# pi_backback.net
KiCad netlist of a schematic drawn in EAGLE
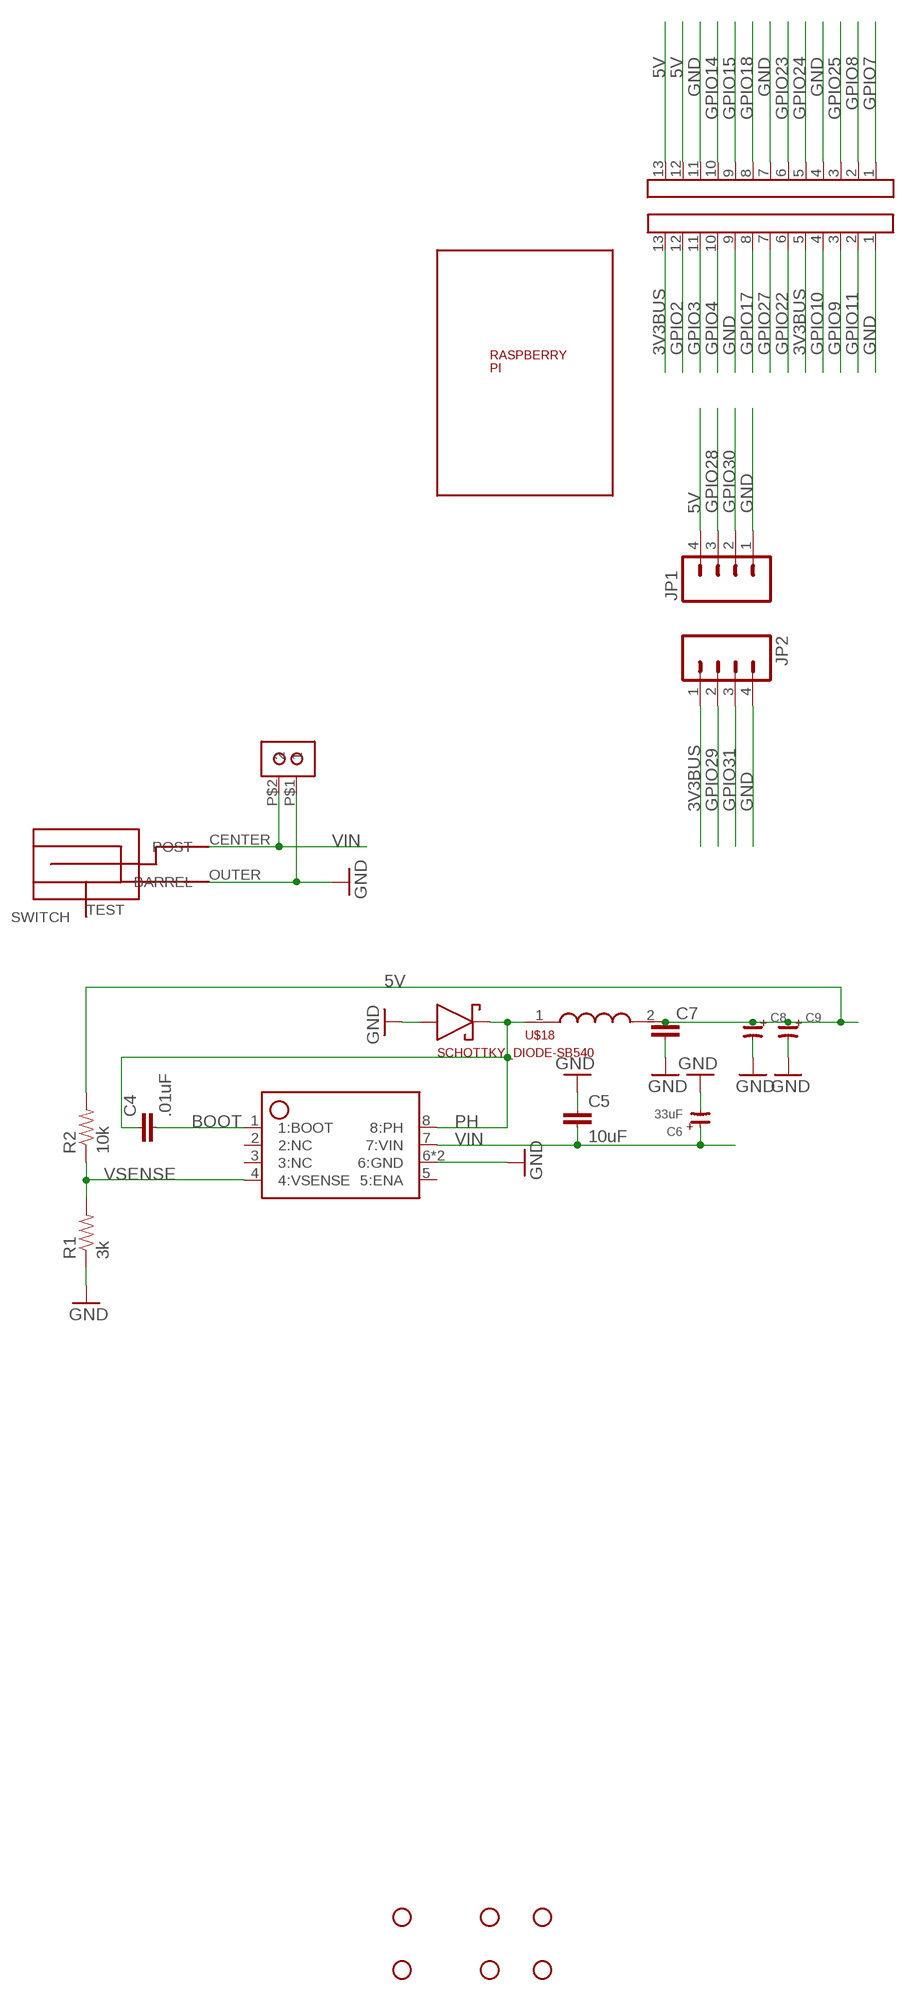
[diagram p0: schematic, sheet 1, part 1 of 2]
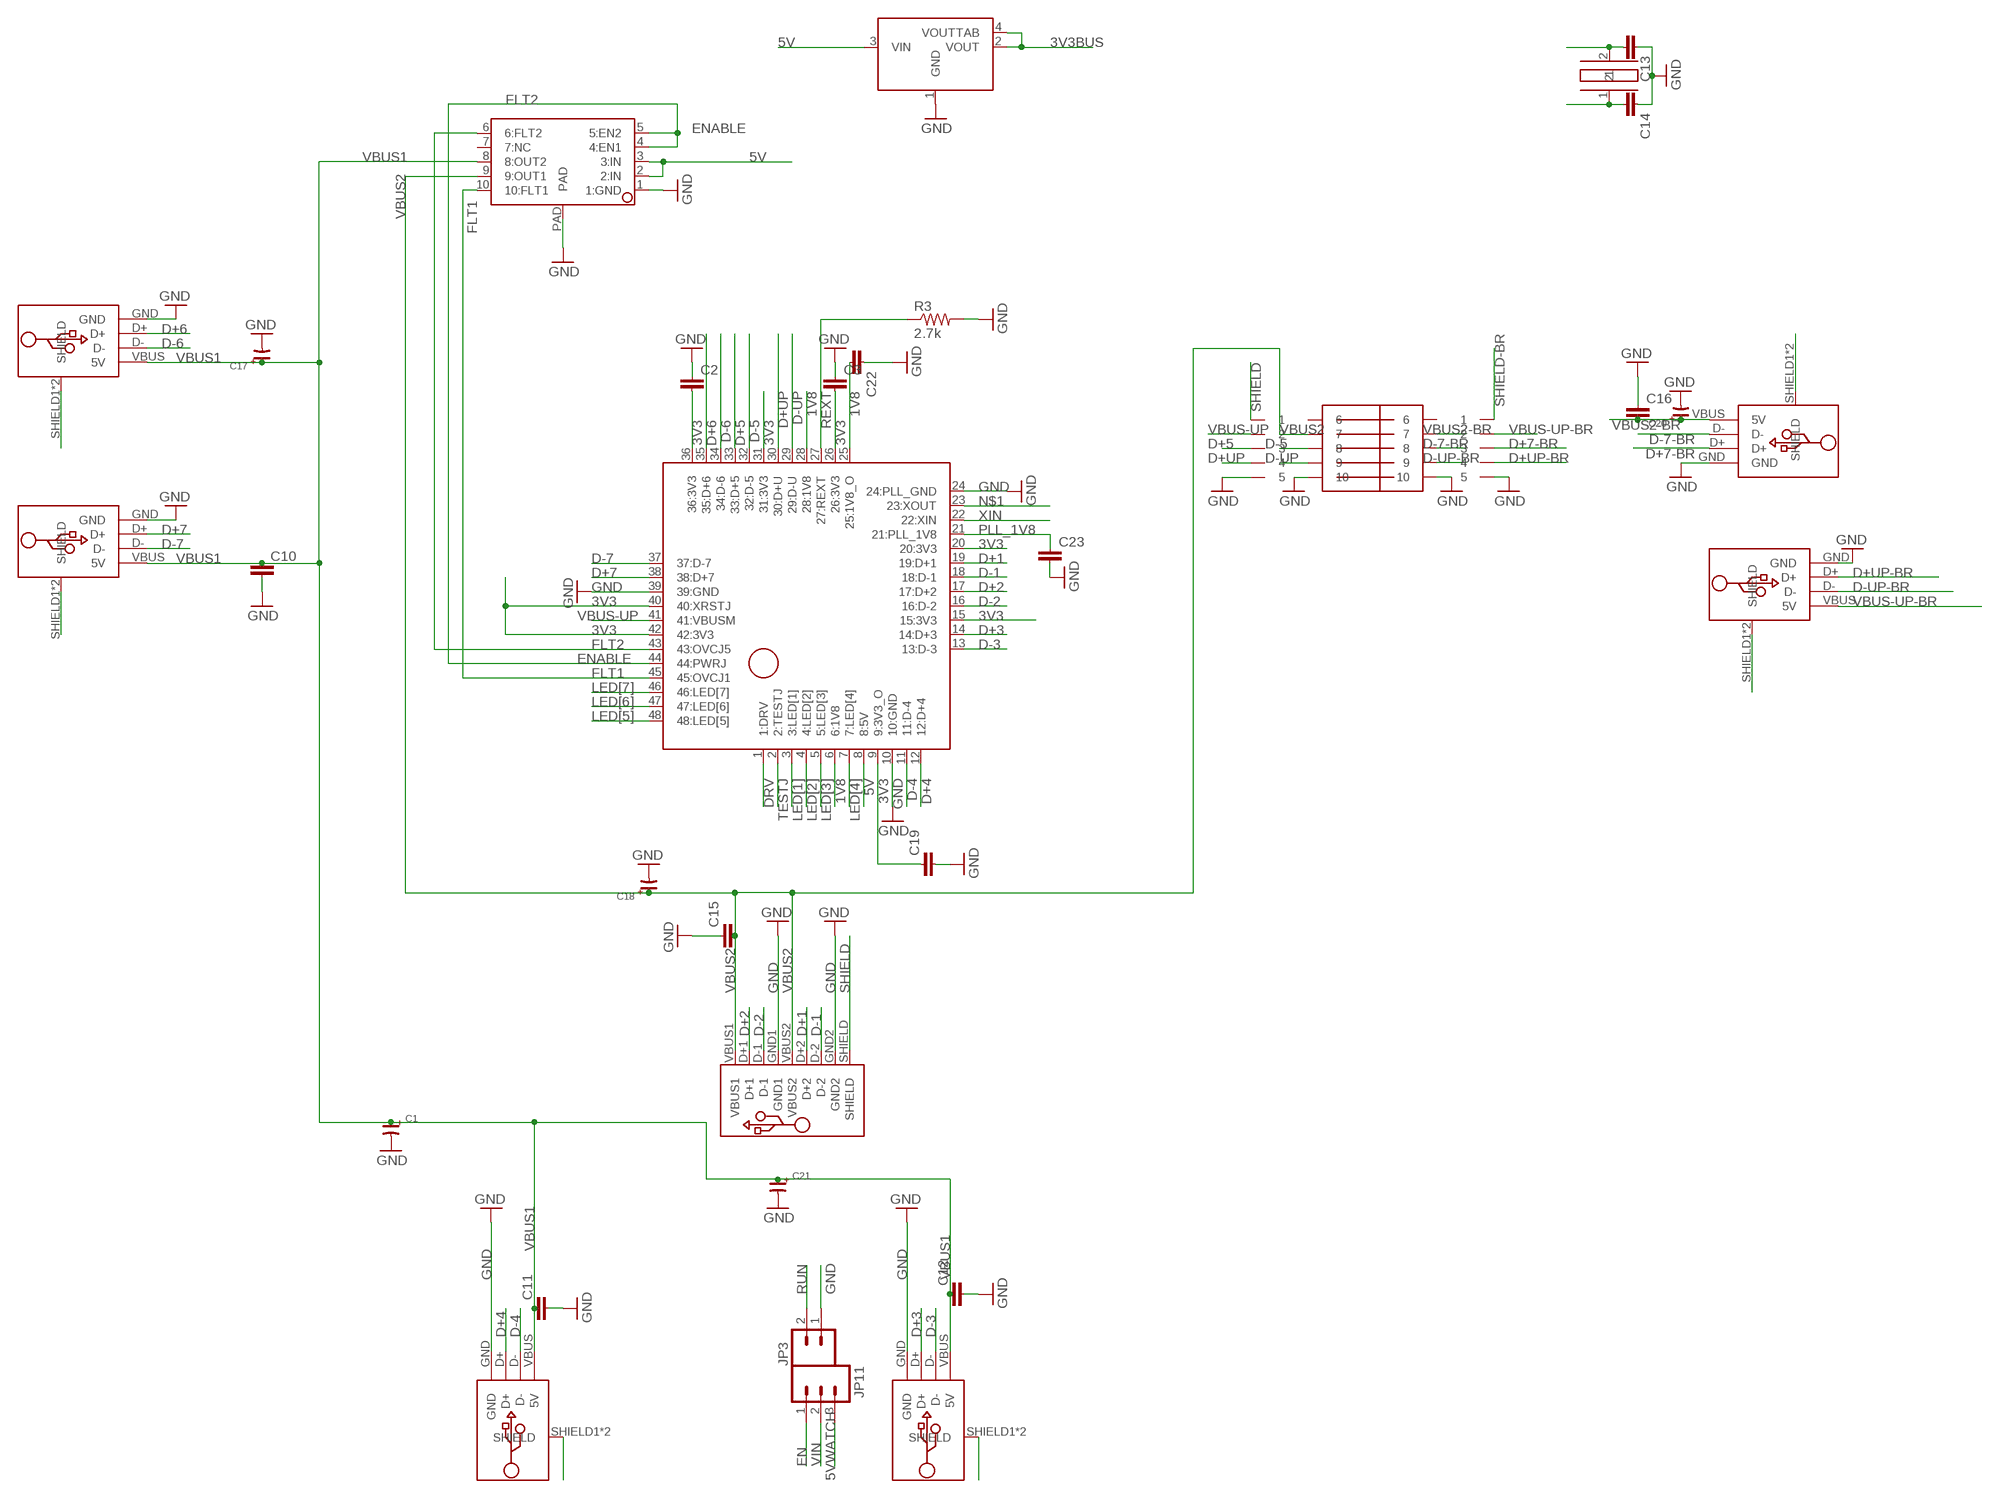
[diagram p1: schematic, sheet 1, part 2 of 2]

(export (version "E")
  (design (tool "Eeschema 10.0.6"))
  (components
    (comp (ref "C1")
      (value "CAPPOL-5X11")
      (footprint "eagle-import:5X11MMCAP")
      (libsource (lib "eagle-import") (part "CAPPOL-5X11"))
    )
    (comp (ref "C2")
      (value "CAP0805")
      (footprint "eagle-import:0805")
      (libsource (lib "eagle-import") (part "CAP0805"))
    )
    (comp (ref "C3")
      (value "CAP0805")
      (footprint "eagle-import:0805")
      (libsource (lib "eagle-import") (part "CAP0805"))
    )
    (comp (ref "C4")
      (value ".01uF")
      (footprint "eagle-import:0603-CAP")
      (libsource (lib "eagle-import") (part "CAP0603-CAP"))
    )
    (comp (ref "C5")
      (value "10uF")
      (footprint "eagle-import:1206")
      (libsource (lib "eagle-import") (part "CAP1206"))
    )
    (comp (ref "C6")
      (value "33uF")
      (footprint "eagle-import:8MMCAP")
      (libsource (lib "eagle-import") (part "CAPPOL-8X11"))
    )
    (comp (ref "C7")
      (value "CAP1206")
      (footprint "eagle-import:1206")
      (libsource (lib "eagle-import") (part "CAP1206"))
    )
    (comp (ref "C8")
      (value "CAPPOL-XX6.3")
      (footprint "eagle-import:6.3MMDIAMELECTROLYTIC")
      (libsource (lib "eagle-import") (part "CAPPOL-XX6.3"))
    )
    (comp (ref "C9")
      (value "CAPPOL-XX6.3")
      (footprint "eagle-import:6.3MMDIAMELECTROLYTIC")
      (libsource (lib "eagle-import") (part "CAPPOL-XX6.3"))
    )
    (comp (ref "C10")
      (value "CAP0805")
      (footprint "eagle-import:0805")
      (libsource (lib "eagle-import") (part "CAP0805"))
    )
    (comp (ref "C11")
      (value "CAP0805")
      (footprint "eagle-import:0805")
      (libsource (lib "eagle-import") (part "CAP0805"))
    )
    (comp (ref "C12")
      (value "CAP0805")
      (footprint "eagle-import:0805")
      (libsource (lib "eagle-import") (part "CAP0805"))
    )
    (comp (ref "C13")
      (value "CAP0603-CAP")
      (footprint "eagle-import:0603-CAP")
      (libsource (lib "eagle-import") (part "CAP0603-CAP"))
    )
    (comp (ref "C14")
      (value "CAP0603-CAP")
      (footprint "eagle-import:0603-CAP")
      (libsource (lib "eagle-import") (part "CAP0603-CAP"))
    )
    (comp (ref "C15")
      (value "CAP0805")
      (footprint "eagle-import:0805")
      (libsource (lib "eagle-import") (part "CAP0805"))
    )
    (comp (ref "C16")
      (value "CAP0805")
      (footprint "eagle-import:0805")
      (libsource (lib "eagle-import") (part "CAP0805"))
    )
    (comp (ref "C17")
      (value "CAPPOL-5X11")
      (footprint "eagle-import:5X11MMCAP")
      (libsource (lib "eagle-import") (part "CAPPOL-5X11"))
    )
    (comp (ref "C18")
      (value "CAPPOL-5X11")
      (footprint "eagle-import:5X11MMCAP")
      (libsource (lib "eagle-import") (part "CAPPOL-5X11"))
    )
    (comp (ref "C19")
      (value "CAP1206")
      (footprint "eagle-import:1206")
      (libsource (lib "eagle-import") (part "CAP1206"))
    )
    (comp (ref "C20")
      (value "CAPPOL-5X11")
      (footprint "eagle-import:5X11MMCAP")
      (libsource (lib "eagle-import") (part "CAPPOL-5X11"))
    )
    (comp (ref "C21")
      (value "CAPPOL-5X11")
      (footprint "eagle-import:5X11MMCAP")
      (libsource (lib "eagle-import") (part "CAPPOL-5X11"))
    )
    (comp (ref "C22")
      (value "CAP1206")
      (footprint "eagle-import:1206")
      (libsource (lib "eagle-import") (part "CAP1206"))
    )
    (comp (ref "C23")
      (value "CAP0805")
      (footprint "eagle-import:0805")
      (libsource (lib "eagle-import") (part "CAP0805"))
    )
    (comp (ref "JP1")
      (value "M04LOCK")
      (footprint "eagle-import:1X04_LOCK")
      (libsource (lib "eagle-import") (part "M04LOCK"))
    )
    (comp (ref "JP2")
      (value "M04LOCK")
      (footprint "eagle-import:1X04_LOCK")
      (libsource (lib "eagle-import") (part "M04LOCK"))
    )
    (comp (ref "JP3")
      (value "M02LOCK")
      (footprint "eagle-import:1X02_LOCK")
      (libsource (lib "eagle-import") (part "M02LOCK"))
    )
    (comp (ref "JP4")
      (value "STAND-OFFTIGHT")
      (footprint "eagle-import:STAND-OFF-TIGHT")
      (libsource (lib "eagle-import") (part "STAND-OFFTIGHT"))
    )
    (comp (ref "JP5")
      (value "STAND-OFFTIGHT")
      (footprint "eagle-import:STAND-OFF-TIGHT")
      (libsource (lib "eagle-import") (part "STAND-OFFTIGHT"))
    )
    (comp (ref "JP6")
      (value "STAND-OFFTIGHT")
      (footprint "eagle-import:STAND-OFF-TIGHT")
      (libsource (lib "eagle-import") (part "STAND-OFFTIGHT"))
    )
    (comp (ref "JP7")
      (value "STAND-OFFTIGHT")
      (footprint "eagle-import:STAND-OFF-TIGHT")
      (libsource (lib "eagle-import") (part "STAND-OFFTIGHT"))
    )
    (comp (ref "JP9")
      (value "STAND-OFFTIGHT")
      (footprint "eagle-import:STAND-OFF-TIGHT")
      (libsource (lib "eagle-import") (part "STAND-OFFTIGHT"))
    )
    (comp (ref "JP10")
      (value "STAND-OFFTIGHT")
      (footprint "eagle-import:STAND-OFF-TIGHT")
      (libsource (lib "eagle-import") (part "STAND-OFFTIGHT"))
    )
    (comp (ref "JP11")
      (value "M03LOCK")
      (footprint "eagle-import:1X03_LOCK")
      (libsource (lib "eagle-import") (part "M03LOCK"))
    )
    (comp (ref "R1")
      (value "3k")
      (footprint "eagle-import:0805")
      (libsource (lib "eagle-import") (part "RESISTOR"))
    )
    (comp (ref "R2")
      (value "10k")
      (footprint "eagle-import:0805")
      (libsource (lib "eagle-import") (part "RESISTOR"))
    )
    (comp (ref "R3")
      (value "2.7k")
      (footprint "eagle-import:0805")
      (libsource (lib "eagle-import") (part "RESISTOR"))
    )
    (comp (ref "U$1")
      (value "RASPBERRY-PI-OUTLINE")
      (footprint "eagle-import:RASPBERRY-PI-REV2-OUTLINE")
      (libsource (lib "eagle-import") (part "RASPBERRY-PI-OUTLINE"))
    )
    (comp (ref "U$2")
      (value "M13")
      (footprint "eagle-import:1X13_LOCK")
      (libsource (lib "eagle-import") (part "M13"))
    )
    (comp (ref "U$3")
      (value "M13")
      (footprint "eagle-import:1X13_LOCK")
      (libsource (lib "eagle-import") (part "M13"))
    )
    (comp (ref "U$4")
      (value "TPS200(2/3)C")
      (footprint "eagle-import:SON-10")
      (libsource (lib "eagle-import") (part "TPS200(2/3)C"))
    )
    (comp (ref "U$5")
      (value "FE2.1-48")
      (footprint "eagle-import:LQFP-48")
      (libsource (lib "eagle-import") (part "FE2.1-48"))
    )
    (comp (ref "U$6")
      (value "USB-A-MALE")
      (footprint "eagle-import:USB-A-MALE")
      (libsource (lib "eagle-import") (part "USB-A-MALE"))
    )
    (comp (ref "U$7")
      (value "SCREWTERM-2MA212-2")
      (footprint "eagle-import:MA212-2")
      (libsource (lib "eagle-import") (part "SCREWTERM-2MA212-2"))
    )
    (comp (ref "U$8")
      (value "USB-A-FEMALE")
      (footprint "eagle-import:USB-A-FEMALE")
      (libsource (lib "eagle-import") (part "USB-A-FEMALE"))
    )
    (comp (ref "U$9")
      (value "USB-A-FEMALE")
      (footprint "eagle-import:USB-A-FEMALE")
      (libsource (lib "eagle-import") (part "USB-A-FEMALE"))
    )
    (comp (ref "U$10")
      (value "USB-A-FEMALE")
      (footprint "eagle-import:USB-A-FEMALE")
      (libsource (lib "eagle-import") (part "USB-A-FEMALE"))
    )
    (comp (ref "U$11")
      (value "USB_HEADER")
      (footprint "eagle-import:USB_HEADER")
      (libsource (lib "eagle-import") (part "USB_HEADER"))
    )
    (comp (ref "U$12")
      (value "USB-A-FEMALE")
      (footprint "eagle-import:USB-A-FEMALE")
      (libsource (lib "eagle-import") (part "USB-A-FEMALE"))
    )
    (comp (ref "U$13")
      (value "TPS5450")
      (footprint "eagle-import:SOIC8-POWERPAD")
      (libsource (lib "eagle-import") (part "TPS5450"))
    )
    (comp (ref "U$14")
      (value "M05X02_FEM-LOCK_RIGHT_ANGLE_FEM")
      (footprint "eagle-import:2X05_LOCK_RIGHT_ANGLE_FEM")
      (libsource (lib "eagle-import") (part "M05X02_FEM-LOCK_RIGHT_ANGLE_FEM"))
    )
    (comp (ref "U$15")
      (value "M05X02_MALE")
      (footprint "eagle-import:2X05_LOCK_RIGHT_ANGLE_MALE")
      (libsource (lib "eagle-import") (part "M05X02_MALE"))
    )
    (comp (ref "U$16")
      (value "USB-A-FEMALE")
      (footprint "eagle-import:USB-A-FEMALE")
      (libsource (lib "eagle-import") (part "USB-A-FEMALE"))
    )
    (comp (ref "U$17")
      (value "POWER-JACK-2.1MM")
      (footprint "eagle-import:2.1MM-POWER-JACK")
      (libsource (lib "eagle-import") (part "POWER-JACK-2.1MM"))
    )
    (comp (ref "U$18")
      (value "INDUCTOR-DR13-RT-A")
      (footprint "eagle-import:DR13-RT-A")
      (libsource (lib "eagle-import") (part "INDUCTOR-DR13-RT-A"))
    )
    (comp (ref "U$19")
      (value "SCHOTTKY_DIODE-SB540")
      (footprint "eagle-import:DO-201-AD")
      (libsource (lib "eagle-import") (part "SCHOTTKY_DIODE-SB540"))
    )
    (comp (ref "U$20")
      (value "CRYSTAL-HC49")
      (footprint "eagle-import:HC49US")
      (libsource (lib "eagle-import") (part "CRYSTAL-HC49"))
    )
    (comp (ref "U$21")
      (value "3V3-LDO-ZLDO1117")
      (footprint "eagle-import:ZLDO1117")
      (libsource (lib "eagle-import") (part "3V3-LDO-ZLDO1117"))
    )
  )
  (nets
    (net (code "1") (name "/1V8") (class "Default")
      (node (ref "C22") (pin "2") (pinfunction "2_2") (pintype "passive"))
      (node (ref "U$5") (pin "25") (pinfunction "25:1V8_O_25") (pintype "bidirectional"))
      (node (ref "U$5") (pin "28") (pinfunction "28:1V8_28") (pintype "bidirectional"))
      (node (ref "U$5") (pin "6") (pinfunction "6:1V8_6") (pintype "bidirectional"))
    )
    (net (code "2") (name "/3V3") (class "Default")
      (node (ref "C19") (pin "1") (pinfunction "1_1") (pintype "passive"))
      (node (ref "C2") (pin "2") (pinfunction "2_2") (pintype "passive"))
      (node (ref "C3") (pin "2") (pinfunction "2_2") (pintype "passive"))
      (node (ref "U$5") (pin "15") (pinfunction "15:3V3_15") (pintype "bidirectional"))
      (node (ref "U$5") (pin "20") (pinfunction "20:3V3_20") (pintype "bidirectional"))
      (node (ref "U$5") (pin "26") (pinfunction "26:3V3_26") (pintype "bidirectional"))
      (node (ref "U$5") (pin "31") (pinfunction "31:3V3_31") (pintype "bidirectional"))
      (node (ref "U$5") (pin "36") (pinfunction "36:3V3_36") (pintype "bidirectional"))
      (node (ref "U$5") (pin "40") (pinfunction "40:XRSTJ_40") (pintype "bidirectional"))
      (node (ref "U$5") (pin "42") (pinfunction "42:3V3_42") (pintype "bidirectional"))
      (node (ref "U$5") (pin "9") (pinfunction "9:3V3_O_9") (pintype "bidirectional"))
    )
    (net (code "3") (name "/3V3BUS") (class "Default")
      (node (ref "JP2") (pin "1") (pinfunction "1_1") (pintype "passive"))
      (node (ref "U$2") (pin "13") (pinfunction "13_13") (pintype "bidirectional"))
      (node (ref "U$2") (pin "5") (pinfunction "5_5") (pintype "bidirectional"))
      (node (ref "U$21") (pin "2") (pinfunction "VOUT_2") (pintype "bidirectional"))
      (node (ref "U$21") (pin "4") (pinfunction "VOUTTAB_4") (pintype "bidirectional"))
    )
    (net (code "4") (name "/5V") (class "Default")
      (node (ref "C7") (pin "1") (pinfunction "1_1") (pintype "passive"))
      (node (ref "C8") (pin "+") (pinfunction "+_+") (pintype "bidirectional"))
      (node (ref "C9") (pin "+") (pinfunction "+_+") (pintype "bidirectional"))
      (node (ref "JP1") (pin "4") (pinfunction "4_4") (pintype "passive"))
      (node (ref "R2") (pin "2") (pinfunction "2_2") (pintype "passive"))
      (node (ref "U$18") (pin "2") (pinfunction "P$2_2") (pintype "bidirectional"))
      (node (ref "U$21") (pin "3") (pinfunction "VIN_3") (pintype "bidirectional"))
      (node (ref "U$3") (pin "12") (pinfunction "12_12") (pintype "bidirectional"))
      (node (ref "U$3") (pin "13") (pinfunction "13_13") (pintype "bidirectional"))
      (node (ref "U$4") (pin "2") (pinfunction "2:IN_2") (pintype "bidirectional"))
      (node (ref "U$4") (pin "3") (pinfunction "3:IN_3") (pintype "bidirectional"))
      (node (ref "U$5") (pin "8") (pinfunction "8:5V_8") (pintype "bidirectional"))
    )
    (net (code "5") (name "/5VWATCH") (class "Default")
      (node (ref "JP11") (pin "3") (pinfunction "3_3") (pintype "passive"))
    )
    (net (code "6") (name "/BOOT") (class "Default")
      (node (ref "C4") (pin "2") (pinfunction "2_2") (pintype "passive"))
      (node (ref "U$13") (pin "1") (pinfunction "1:BOOT_1") (pintype "bidirectional"))
    )
    (net (code "7") (name "/D+1") (class "Default")
      (node (ref "U$11") (pin "D+2") (pinfunction "D+2_D+2") (pintype "bidirectional"))
      (node (ref "U$5") (pin "19") (pinfunction "19:D+1_19") (pintype "bidirectional"))
    )
    (net (code "8") (name "/D+2") (class "Default")
      (node (ref "U$11") (pin "D+1") (pinfunction "D+1_D+1") (pintype "bidirectional"))
      (node (ref "U$5") (pin "17") (pinfunction "17:D+2_17") (pintype "bidirectional"))
    )
    (net (code "9") (name "/D+3") (class "Default")
      (node (ref "U$12") (pin "D+") (pinfunction "D+_D+") (pintype "bidirectional"))
      (node (ref "U$5") (pin "14") (pinfunction "14:D+3_14") (pintype "bidirectional"))
    )
    (net (code "10") (name "/D+4") (class "Default")
      (node (ref "U$16") (pin "D+") (pinfunction "D+_D+") (pintype "bidirectional"))
      (node (ref "U$5") (pin "12") (pinfunction "12:D+4_12") (pintype "bidirectional"))
    )
    (net (code "11") (name "/D+5") (class "Default")
      (node (ref "U$14") (pin "3") (pinfunction "3_3") (pintype "bidirectional"))
      (node (ref "U$5") (pin "33") (pinfunction "33:D+5_33") (pintype "bidirectional"))
    )
    (net (code "12") (name "/D+6") (class "Default")
      (node (ref "U$5") (pin "35") (pinfunction "35:D+6_35") (pintype "bidirectional"))
      (node (ref "U$9") (pin "D+") (pinfunction "D+_D+") (pintype "bidirectional"))
    )
    (net (code "13") (name "/D+7") (class "Default")
      (node (ref "U$5") (pin "38") (pinfunction "38:D+7_38") (pintype "bidirectional"))
      (node (ref "U$8") (pin "D+") (pinfunction "D+_D+") (pintype "bidirectional"))
    )
    (net (code "14") (name "/D+7-BR") (class "Default")
      (node (ref "U$10") (pin "D+") (pinfunction "D+_D+") (pintype "bidirectional"))
      (node (ref "U$15") (pin "3") (pinfunction "3_3") (pintype "bidirectional"))
    )
    (net (code "15") (name "/D+UP") (class "Default")
      (node (ref "U$14") (pin "4") (pinfunction "4_4") (pintype "bidirectional"))
      (node (ref "U$5") (pin "30") (pinfunction "30:D+U_30") (pintype "bidirectional"))
    )
    (net (code "16") (name "/D+UP-BR") (class "Default")
      (node (ref "U$15") (pin "4") (pinfunction "4_4") (pintype "bidirectional"))
      (node (ref "U$6") (pin "D+") (pinfunction "D+_D+") (pintype "bidirectional"))
    )
    (net (code "17") (name "/D-1") (class "Default")
      (node (ref "U$11") (pin "D-2") (pinfunction "D-2_D-2") (pintype "bidirectional"))
      (node (ref "U$5") (pin "18") (pinfunction "18:D-1_18") (pintype "bidirectional"))
    )
    (net (code "18") (name "/D-2") (class "Default")
      (node (ref "U$11") (pin "D-1") (pinfunction "D-1_D-1") (pintype "bidirectional"))
      (node (ref "U$5") (pin "16") (pinfunction "16:D-2_16") (pintype "bidirectional"))
    )
    (net (code "19") (name "/D-3") (class "Default")
      (node (ref "U$12") (pin "D-") (pinfunction "D-_D-") (pintype "bidirectional"))
      (node (ref "U$5") (pin "13") (pinfunction "13:D-3_13") (pintype "bidirectional"))
    )
    (net (code "20") (name "/D-4") (class "Default")
      (node (ref "U$16") (pin "D-") (pinfunction "D-_D-") (pintype "bidirectional"))
      (node (ref "U$5") (pin "11") (pinfunction "11:D-4_11") (pintype "bidirectional"))
    )
    (net (code "21") (name "/D-5") (class "Default")
      (node (ref "U$14") (pin "8") (pinfunction "8_8") (pintype "bidirectional"))
      (node (ref "U$5") (pin "32") (pinfunction "32:D-5_32") (pintype "bidirectional"))
    )
    (net (code "22") (name "/D-6") (class "Default")
      (node (ref "U$5") (pin "34") (pinfunction "34:D-6_34") (pintype "bidirectional"))
      (node (ref "U$9") (pin "D-") (pinfunction "D-_D-") (pintype "bidirectional"))
    )
    (net (code "23") (name "/D-7") (class "Default")
      (node (ref "U$5") (pin "37") (pinfunction "37:D-7_37") (pintype "bidirectional"))
      (node (ref "U$8") (pin "D-") (pinfunction "D-_D-") (pintype "bidirectional"))
    )
    (net (code "24") (name "/D-7-BR") (class "Default")
      (node (ref "U$10") (pin "D-") (pinfunction "D-_D-") (pintype "bidirectional"))
      (node (ref "U$15") (pin "8") (pinfunction "8_8") (pintype "bidirectional"))
    )
    (net (code "25") (name "/D-UP") (class "Default")
      (node (ref "U$14") (pin "9") (pinfunction "9_9") (pintype "bidirectional"))
      (node (ref "U$5") (pin "29") (pinfunction "29:D-U_29") (pintype "bidirectional"))
    )
    (net (code "26") (name "/D-UP-BR") (class "Default")
      (node (ref "U$15") (pin "9") (pinfunction "9_9") (pintype "bidirectional"))
      (node (ref "U$6") (pin "D-") (pinfunction "D-_D-") (pintype "bidirectional"))
    )
    (net (code "27") (name "/DRV") (class "Default")
      (node (ref "U$5") (pin "1") (pinfunction "1:DRV_1") (pintype "bidirectional"))
    )
    (net (code "28") (name "/EN") (class "Default")
      (node (ref "JP11") (pin "1") (pinfunction "1_1") (pintype "passive"))
    )
    (net (code "29") (name "/ENABLE") (class "Default")
      (node (ref "U$4") (pin "4") (pinfunction "4:EN1_4") (pintype "bidirectional"))
      (node (ref "U$4") (pin "5") (pinfunction "5:EN2_5") (pintype "bidirectional"))
      (node (ref "U$5") (pin "44") (pinfunction "44:PWRJ_44") (pintype "bidirectional"))
    )
    (net (code "30") (name "/FLT1") (class "Default")
      (node (ref "U$4") (pin "10") (pinfunction "10:FLT1_10") (pintype "bidirectional"))
      (node (ref "U$5") (pin "45") (pinfunction "45:OVCJ1_45") (pintype "bidirectional"))
    )
    (net (code "31") (name "/FLT2") (class "Default")
      (node (ref "U$4") (pin "6") (pinfunction "6:FLT2_6") (pintype "bidirectional"))
      (node (ref "U$5") (pin "43") (pinfunction "43:OVCJ5_43") (pintype "bidirectional"))
    )
    (net (code "32") (name "/GPIO2") (class "Default")
      (node (ref "U$2") (pin "12") (pinfunction "12_12") (pintype "bidirectional"))
    )
    (net (code "33") (name "/GPIO3") (class "Default")
      (node (ref "U$2") (pin "11") (pinfunction "11_11") (pintype "bidirectional"))
    )
    (net (code "34") (name "/GPIO4") (class "Default")
      (node (ref "U$2") (pin "10") (pinfunction "10_10") (pintype "bidirectional"))
    )
    (net (code "35") (name "/GPIO7") (class "Default")
      (node (ref "U$3") (pin "1") (pinfunction "1_1") (pintype "bidirectional"))
    )
    (net (code "36") (name "/GPIO8") (class "Default")
      (node (ref "U$3") (pin "2") (pinfunction "2_2") (pintype "bidirectional"))
    )
    (net (code "37") (name "/GPIO9") (class "Default")
      (node (ref "U$2") (pin "3") (pinfunction "3_3") (pintype "bidirectional"))
    )
    (net (code "38") (name "/GPIO10") (class "Default")
      (node (ref "U$2") (pin "4") (pinfunction "4_4") (pintype "bidirectional"))
    )
    (net (code "39") (name "/GPIO11") (class "Default")
      (node (ref "U$2") (pin "2") (pinfunction "2_2") (pintype "bidirectional"))
    )
    (net (code "40") (name "/GPIO14") (class "Default")
      (node (ref "U$3") (pin "10") (pinfunction "10_10") (pintype "bidirectional"))
    )
    (net (code "41") (name "/GPIO15") (class "Default")
      (node (ref "U$3") (pin "9") (pinfunction "9_9") (pintype "bidirectional"))
    )
    (net (code "42") (name "/GPIO17") (class "Default")
      (node (ref "U$2") (pin "8") (pinfunction "8_8") (pintype "bidirectional"))
    )
    (net (code "43") (name "/GPIO18") (class "Default")
      (node (ref "U$3") (pin "8") (pinfunction "8_8") (pintype "bidirectional"))
    )
    (net (code "44") (name "/GPIO22") (class "Default")
      (node (ref "U$2") (pin "6") (pinfunction "6_6") (pintype "bidirectional"))
    )
    (net (code "45") (name "/GPIO23") (class "Default")
      (node (ref "U$3") (pin "6") (pinfunction "6_6") (pintype "bidirectional"))
    )
    (net (code "46") (name "/GPIO24") (class "Default")
      (node (ref "U$3") (pin "5") (pinfunction "5_5") (pintype "bidirectional"))
    )
    (net (code "47") (name "/GPIO25") (class "Default")
      (node (ref "U$3") (pin "3") (pinfunction "3_3") (pintype "bidirectional"))
    )
    (net (code "48") (name "/GPIO27") (class "Default")
      (node (ref "U$2") (pin "7") (pinfunction "7_7") (pintype "bidirectional"))
    )
    (net (code "49") (name "/GPIO28") (class "Default")
      (node (ref "JP1") (pin "3") (pinfunction "3_3") (pintype "passive"))
    )
    (net (code "50") (name "/GPIO29") (class "Default")
      (node (ref "JP2") (pin "2") (pinfunction "2_2") (pintype "passive"))
    )
    (net (code "51") (name "/GPIO30") (class "Default")
      (node (ref "JP1") (pin "2") (pinfunction "2_2") (pintype "passive"))
    )
    (net (code "52") (name "/GPIO31") (class "Default")
      (node (ref "JP2") (pin "3") (pinfunction "3_3") (pintype "passive"))
    )
    (net (code "53") (name "/LED[1]") (class "Default")
      (node (ref "U$5") (pin "3") (pinfunction "3:LED[1]_3") (pintype "bidirectional"))
    )
    (net (code "54") (name "/LED[2]") (class "Default")
      (node (ref "U$5") (pin "4") (pinfunction "4:LED[2]_4") (pintype "bidirectional"))
    )
    (net (code "55") (name "/LED[3]") (class "Default")
      (node (ref "U$5") (pin "5") (pinfunction "5:LED[3]_5") (pintype "bidirectional"))
    )
    (net (code "56") (name "/LED[4]") (class "Default")
      (node (ref "U$5") (pin "7") (pinfunction "7:LED[4]_7") (pintype "bidirectional"))
    )
    (net (code "57") (name "/LED[5]") (class "Default")
      (node (ref "U$5") (pin "48") (pinfunction "48:LED[5]_48") (pintype "bidirectional"))
    )
    (net (code "58") (name "/LED[6]") (class "Default")
      (node (ref "U$5") (pin "47") (pinfunction "47:LED[6]_47") (pintype "bidirectional"))
    )
    (net (code "59") (name "/LED[7]") (class "Default")
      (node (ref "U$5") (pin "46") (pinfunction "46:LED[7]_46") (pintype "bidirectional"))
    )
    (net (code "60") (name "/N$1") (class "Default")
      (node (ref "U$5") (pin "23") (pinfunction "23:XOUT_23") (pintype "bidirectional"))
    )
    (net (code "61") (name "/PH") (class "Default")
      (node (ref "C4") (pin "1") (pinfunction "1_1") (pintype "passive"))
      (node (ref "U$13") (pin "8") (pinfunction "8:PH_8") (pintype "bidirectional"))
      (node (ref "U$18") (pin "1") (pinfunction "P$1_1") (pintype "bidirectional"))
      (node (ref "U$19") (pin "C") (pinfunction "CATHODE_C") (pintype "bidirectional"))
    )
    (net (code "62") (name "/PLL_1V8") (class "Default")
      (node (ref "C23") (pin "1") (pinfunction "1_1") (pintype "passive"))
      (node (ref "U$5") (pin "21") (pinfunction "21:PLL_1V8_21") (pintype "bidirectional"))
    )
    (net (code "63") (name "/REXT") (class "Default")
      (node (ref "R3") (pin "1") (pinfunction "1_1") (pintype "passive"))
      (node (ref "U$5") (pin "27") (pinfunction "27:REXT_27") (pintype "bidirectional"))
    )
    (net (code "64") (name "/RUN") (class "Default")
      (node (ref "JP3") (pin "2") (pinfunction "2_2") (pintype "passive"))
    )
    (net (code "65") (name "/SHIELD") (class "Default")
      (node (ref "U$11") (pin "SHIELD") (pinfunction "SHIELD_SHIELD") (pintype "bidirectional"))
      (node (ref "U$12") (pin "SHIELD1") (pinfunction "SHIELD_SHIELD1") (pintype "bidirectional"))
      (node (ref "U$12") (pin "SHIELD2") (pinfunction "SHIELD_SHIELD2") (pintype "bidirectional"))
      (node (ref "U$14") (pin "1") (pinfunction "1_1") (pintype "bidirectional"))
      (node (ref "U$16") (pin "SHIELD1") (pinfunction "SHIELD_SHIELD1") (pintype "bidirectional"))
      (node (ref "U$16") (pin "SHIELD2") (pinfunction "SHIELD_SHIELD2") (pintype "bidirectional"))
      (node (ref "U$8") (pin "SHIELD1") (pinfunction "SHIELD_SHIELD1") (pintype "bidirectional"))
      (node (ref "U$8") (pin "SHIELD2") (pinfunction "SHIELD_SHIELD2") (pintype "bidirectional"))
      (node (ref "U$9") (pin "SHIELD1") (pinfunction "SHIELD_SHIELD1") (pintype "bidirectional"))
      (node (ref "U$9") (pin "SHIELD2") (pinfunction "SHIELD_SHIELD2") (pintype "bidirectional"))
    )
    (net (code "66") (name "/SHIELD-BR") (class "Default")
      (node (ref "U$10") (pin "SHIELD1") (pinfunction "SHIELD_SHIELD1") (pintype "bidirectional"))
      (node (ref "U$10") (pin "SHIELD2") (pinfunction "SHIELD_SHIELD2") (pintype "bidirectional"))
      (node (ref "U$15") (pin "1") (pinfunction "1_1") (pintype "bidirectional"))
      (node (ref "U$6") (pin "SHIELD1") (pinfunction "SHIELD_SHIELD1") (pintype "bidirectional"))
      (node (ref "U$6") (pin "SHIELD2") (pinfunction "SHIELD_SHIELD2") (pintype "bidirectional"))
    )
    (net (code "67") (name "/TESTJ") (class "Default")
      (node (ref "U$5") (pin "2") (pinfunction "2:TESTJ_2") (pintype "bidirectional"))
    )
    (net (code "68") (name "/VBUS-UP") (class "Default")
      (node (ref "U$14") (pin "2") (pinfunction "2_2") (pintype "bidirectional"))
      (node (ref "U$5") (pin "41") (pinfunction "41:VBUSM_41") (pintype "bidirectional"))
    )
    (net (code "69") (name "/VBUS-UP-BR") (class "Default")
      (node (ref "U$15") (pin "2") (pinfunction "2_2") (pintype "bidirectional"))
      (node (ref "U$6") (pin "VBUS") (pinfunction "5V_VBUS") (pintype "bidirectional"))
    )
    (net (code "70") (name "/VBUS1") (class "Default")
      (node (ref "C1") (pin "+") (pinfunction "+_+") (pintype "bidirectional"))
      (node (ref "C10") (pin "1") (pinfunction "1_1") (pintype "passive"))
      (node (ref "C11") (pin "1") (pinfunction "1_1") (pintype "passive"))
      (node (ref "C12") (pin "1") (pinfunction "1_1") (pintype "passive"))
      (node (ref "C17") (pin "+") (pinfunction "+_+") (pintype "bidirectional"))
      (node (ref "C21") (pin "+") (pinfunction "+_+") (pintype "bidirectional"))
      (node (ref "U$12") (pin "VBUS") (pinfunction "5V_VBUS") (pintype "bidirectional"))
      (node (ref "U$16") (pin "VBUS") (pinfunction "5V_VBUS") (pintype "bidirectional"))
      (node (ref "U$4") (pin "8") (pinfunction "8:OUT2_8") (pintype "bidirectional"))
      (node (ref "U$8") (pin "VBUS") (pinfunction "5V_VBUS") (pintype "bidirectional"))
      (node (ref "U$9") (pin "VBUS") (pinfunction "5V_VBUS") (pintype "bidirectional"))
    )
    (net (code "71") (name "/VBUS2") (class "Default")
      (node (ref "C15") (pin "2") (pinfunction "2_2") (pintype "passive"))
      (node (ref "C18") (pin "+") (pinfunction "+_+") (pintype "bidirectional"))
      (node (ref "U$11") (pin "VBUS1") (pinfunction "VBUS1_VBUS1") (pintype "bidirectional"))
      (node (ref "U$11") (pin "VBUS2") (pinfunction "VBUS2_VBUS2") (pintype "bidirectional"))
      (node (ref "U$14") (pin "7") (pinfunction "7_7") (pintype "bidirectional"))
      (node (ref "U$4") (pin "9") (pinfunction "9:OUT1_9") (pintype "bidirectional"))
    )
    (net (code "72") (name "/VBUS2-BR") (class "Default")
      (node (ref "C16") (pin "2") (pinfunction "2_2") (pintype "passive"))
      (node (ref "C20") (pin "+") (pinfunction "+_+") (pintype "bidirectional"))
      (node (ref "U$10") (pin "VBUS") (pinfunction "5V_VBUS") (pintype "bidirectional"))
      (node (ref "U$15") (pin "7") (pinfunction "7_7") (pintype "bidirectional"))
    )
    (net (code "73") (name "/VIN") (class "Default")
      (node (ref "C5") (pin "2") (pinfunction "2_2") (pintype "passive"))
      (node (ref "C6") (pin "+") (pinfunction "+_+") (pintype "bidirectional"))
      (node (ref "JP11") (pin "2") (pinfunction "2_2") (pintype "passive"))
      (node (ref "U$13") (pin "7") (pinfunction "7:VIN_7") (pintype "bidirectional"))
      (node (ref "U$17") (pin "CENTER") (pinfunction "POST_CENTER") (pintype "bidirectional"))
      (node (ref "U$7") (pin "P$2") (pinfunction "2_P$2") (pintype "bidirectional"))
    )
    (net (code "74") (name "/VSENSE") (class "Default")
      (node (ref "R1") (pin "2") (pinfunction "2_2") (pintype "passive"))
      (node (ref "R2") (pin "1") (pinfunction "1_1") (pintype "passive"))
      (node (ref "U$13") (pin "4") (pinfunction "4:VSENSE_4") (pintype "bidirectional"))
    )
    (net (code "75") (name "/XIN") (class "Default")
      (node (ref "U$5") (pin "22") (pinfunction "22:XIN_22") (pintype "bidirectional"))
    )
    (net (code "76") (name "GND") (class "Default")
      (node (ref "C1") (pin "-") (pinfunction "-_-") (pintype "bidirectional"))
      (node (ref "C10") (pin "2") (pinfunction "2_2") (pintype "passive"))
      (node (ref "C11") (pin "2") (pinfunction "2_2") (pintype "passive"))
      (node (ref "C12") (pin "2") (pinfunction "2_2") (pintype "passive"))
      (node (ref "C13") (pin "1") (pinfunction "1_1") (pintype "passive"))
      (node (ref "C14") (pin "1") (pinfunction "1_1") (pintype "passive"))
      (node (ref "C15") (pin "1") (pinfunction "1_1") (pintype "passive"))
      (node (ref "C16") (pin "1") (pinfunction "1_1") (pintype "passive"))
      (node (ref "C17") (pin "-") (pinfunction "-_-") (pintype "bidirectional"))
      (node (ref "C18") (pin "-") (pinfunction "-_-") (pintype "bidirectional"))
      (node (ref "C19") (pin "2") (pinfunction "2_2") (pintype "passive"))
      (node (ref "C2") (pin "1") (pinfunction "1_1") (pintype "passive"))
      (node (ref "C20") (pin "-") (pinfunction "-_-") (pintype "bidirectional"))
      (node (ref "C21") (pin "-") (pinfunction "-_-") (pintype "bidirectional"))
      (node (ref "C22") (pin "1") (pinfunction "1_1") (pintype "passive"))
      (node (ref "C23") (pin "2") (pinfunction "2_2") (pintype "passive"))
      (node (ref "C3") (pin "1") (pinfunction "1_1") (pintype "passive"))
      (node (ref "C5") (pin "1") (pinfunction "1_1") (pintype "passive"))
      (node (ref "C6") (pin "-") (pinfunction "-_-") (pintype "bidirectional"))
      (node (ref "C7") (pin "2") (pinfunction "2_2") (pintype "passive"))
      (node (ref "C8") (pin "-") (pinfunction "-_-") (pintype "bidirectional"))
      (node (ref "C9") (pin "-") (pinfunction "-_-") (pintype "bidirectional"))
      (node (ref "JP1") (pin "1") (pinfunction "1_1") (pintype "passive"))
      (node (ref "JP2") (pin "4") (pinfunction "4_4") (pintype "passive"))
      (node (ref "JP3") (pin "1") (pinfunction "1_1") (pintype "passive"))
      (node (ref "R1") (pin "1") (pinfunction "1_1") (pintype "passive"))
      (node (ref "R3") (pin "2") (pinfunction "2_2") (pintype "passive"))
      (node (ref "U$10") (pin "GND") (pinfunction "GND_GND") (pintype "bidirectional"))
      (node (ref "U$11") (pin "GND1") (pinfunction "GND1_GND1") (pintype "bidirectional"))
      (node (ref "U$11") (pin "GND2") (pinfunction "GND2_GND2") (pintype "bidirectional"))
      (node (ref "U$12") (pin "GND") (pinfunction "GND_GND") (pintype "bidirectional"))
      (node (ref "U$13") (pin "6") (pinfunction "6:GND_6") (pintype "bidirectional"))
      (node (ref "U$13") (pin "PAD") (pinfunction "6:GND_PAD") (pintype "bidirectional"))
      (node (ref "U$14") (pin "10") (pinfunction "10_10") (pintype "bidirectional"))
      (node (ref "U$14") (pin "5") (pinfunction "5_5") (pintype "bidirectional"))
      (node (ref "U$15") (pin "10") (pinfunction "10_10") (pintype "bidirectional"))
      (node (ref "U$15") (pin "5") (pinfunction "5_5") (pintype "bidirectional"))
      (node (ref "U$16") (pin "GND") (pinfunction "GND_GND") (pintype "bidirectional"))
      (node (ref "U$17") (pin "OUTER") (pinfunction "BARREL_OUTER") (pintype "bidirectional"))
      (node (ref "U$19") (pin "A") (pinfunction "ANODE_A") (pintype "bidirectional"))
      (node (ref "U$2") (pin "1") (pinfunction "1_1") (pintype "bidirectional"))
      (node (ref "U$2") (pin "9") (pinfunction "9_9") (pintype "bidirectional"))
      (node (ref "U$21") (pin "1") (pinfunction "GND_1") (pintype "bidirectional"))
      (node (ref "U$3") (pin "11") (pinfunction "11_11") (pintype "bidirectional"))
      (node (ref "U$3") (pin "4") (pinfunction "4_4") (pintype "bidirectional"))
      (node (ref "U$3") (pin "7") (pinfunction "7_7") (pintype "bidirectional"))
      (node (ref "U$4") (pin "1") (pinfunction "1:GND_1") (pintype "bidirectional"))
      (node (ref "U$4") (pin "PAD") (pinfunction "PAD_PAD") (pintype "bidirectional"))
      (node (ref "U$5") (pin "10") (pinfunction "10:GND_10") (pintype "bidirectional"))
      (node (ref "U$5") (pin "24") (pinfunction "24:PLL_GND_24") (pintype "bidirectional"))
      (node (ref "U$5") (pin "39") (pinfunction "39:GND_39") (pintype "bidirectional"))
      (node (ref "U$6") (pin "GND") (pinfunction "GND_GND") (pintype "bidirectional"))
      (node (ref "U$7") (pin "P$1") (pinfunction "1_P$1") (pintype "bidirectional"))
      (node (ref "U$8") (pin "GND") (pinfunction "GND_GND") (pintype "bidirectional"))
      (node (ref "U$9") (pin "GND") (pinfunction "GND_GND") (pintype "bidirectional"))
    )
    (net (code "77") (name "Net-(C13-Pad2)") (class "Default")
      (node (ref "C13") (pin "2") (pinfunction "2_2") (pintype "passive"))
      (node (ref "U$20") (pin "2") (pinfunction "2_2") (pintype "bidirectional"))
    )
    (net (code "78") (name "Net-(C14-Pad2)") (class "Default")
      (node (ref "C14") (pin "2") (pinfunction "2_2") (pintype "passive"))
      (node (ref "U$20") (pin "1") (pinfunction "1_1") (pintype "bidirectional"))
    )
    (net (code "79") (name "unconnected-(U$4-7:NC-Pad7)") (class "Default")
      (node (ref "U$4") (pin "7") (pinfunction "7:NC_7") (pintype "bidirectional"))
    )
    (net (code "80") (name "unconnected-(U$13-2:NC-Pad2)") (class "Default")
      (node (ref "U$13") (pin "2") (pinfunction "2:NC_2") (pintype "bidirectional"))
    )
    (net (code "81") (name "unconnected-(U$13-3:NC-Pad3)") (class "Default")
      (node (ref "U$13") (pin "3") (pinfunction "3:NC_3") (pintype "bidirectional"))
    )
    (net (code "82") (name "unconnected-(U$13-5:ENA-Pad5)") (class "Default")
      (node (ref "U$13") (pin "5") (pinfunction "5:ENA_5") (pintype "bidirectional"))
    )
    (net (code "83") (name "unconnected-(U$14-Pad6)") (class "Default")
      (node (ref "U$14") (pin "6") (pinfunction "6_6") (pintype "bidirectional"))
    )
    (net (code "84") (name "unconnected-(U$15-Pad6)") (class "Default")
      (node (ref "U$15") (pin "6") (pinfunction "6_6") (pintype "bidirectional"))
    )
    (net (code "85") (name "unconnected-(U$17-SWITCH-PadTEST)") (class "Default")
      (node (ref "U$17") (pin "TEST") (pinfunction "SWITCH_TEST") (pintype "bidirectional"))
    )
  )
)
